# M720.net
KiCad netlist of a schematic drawn in EAGLE
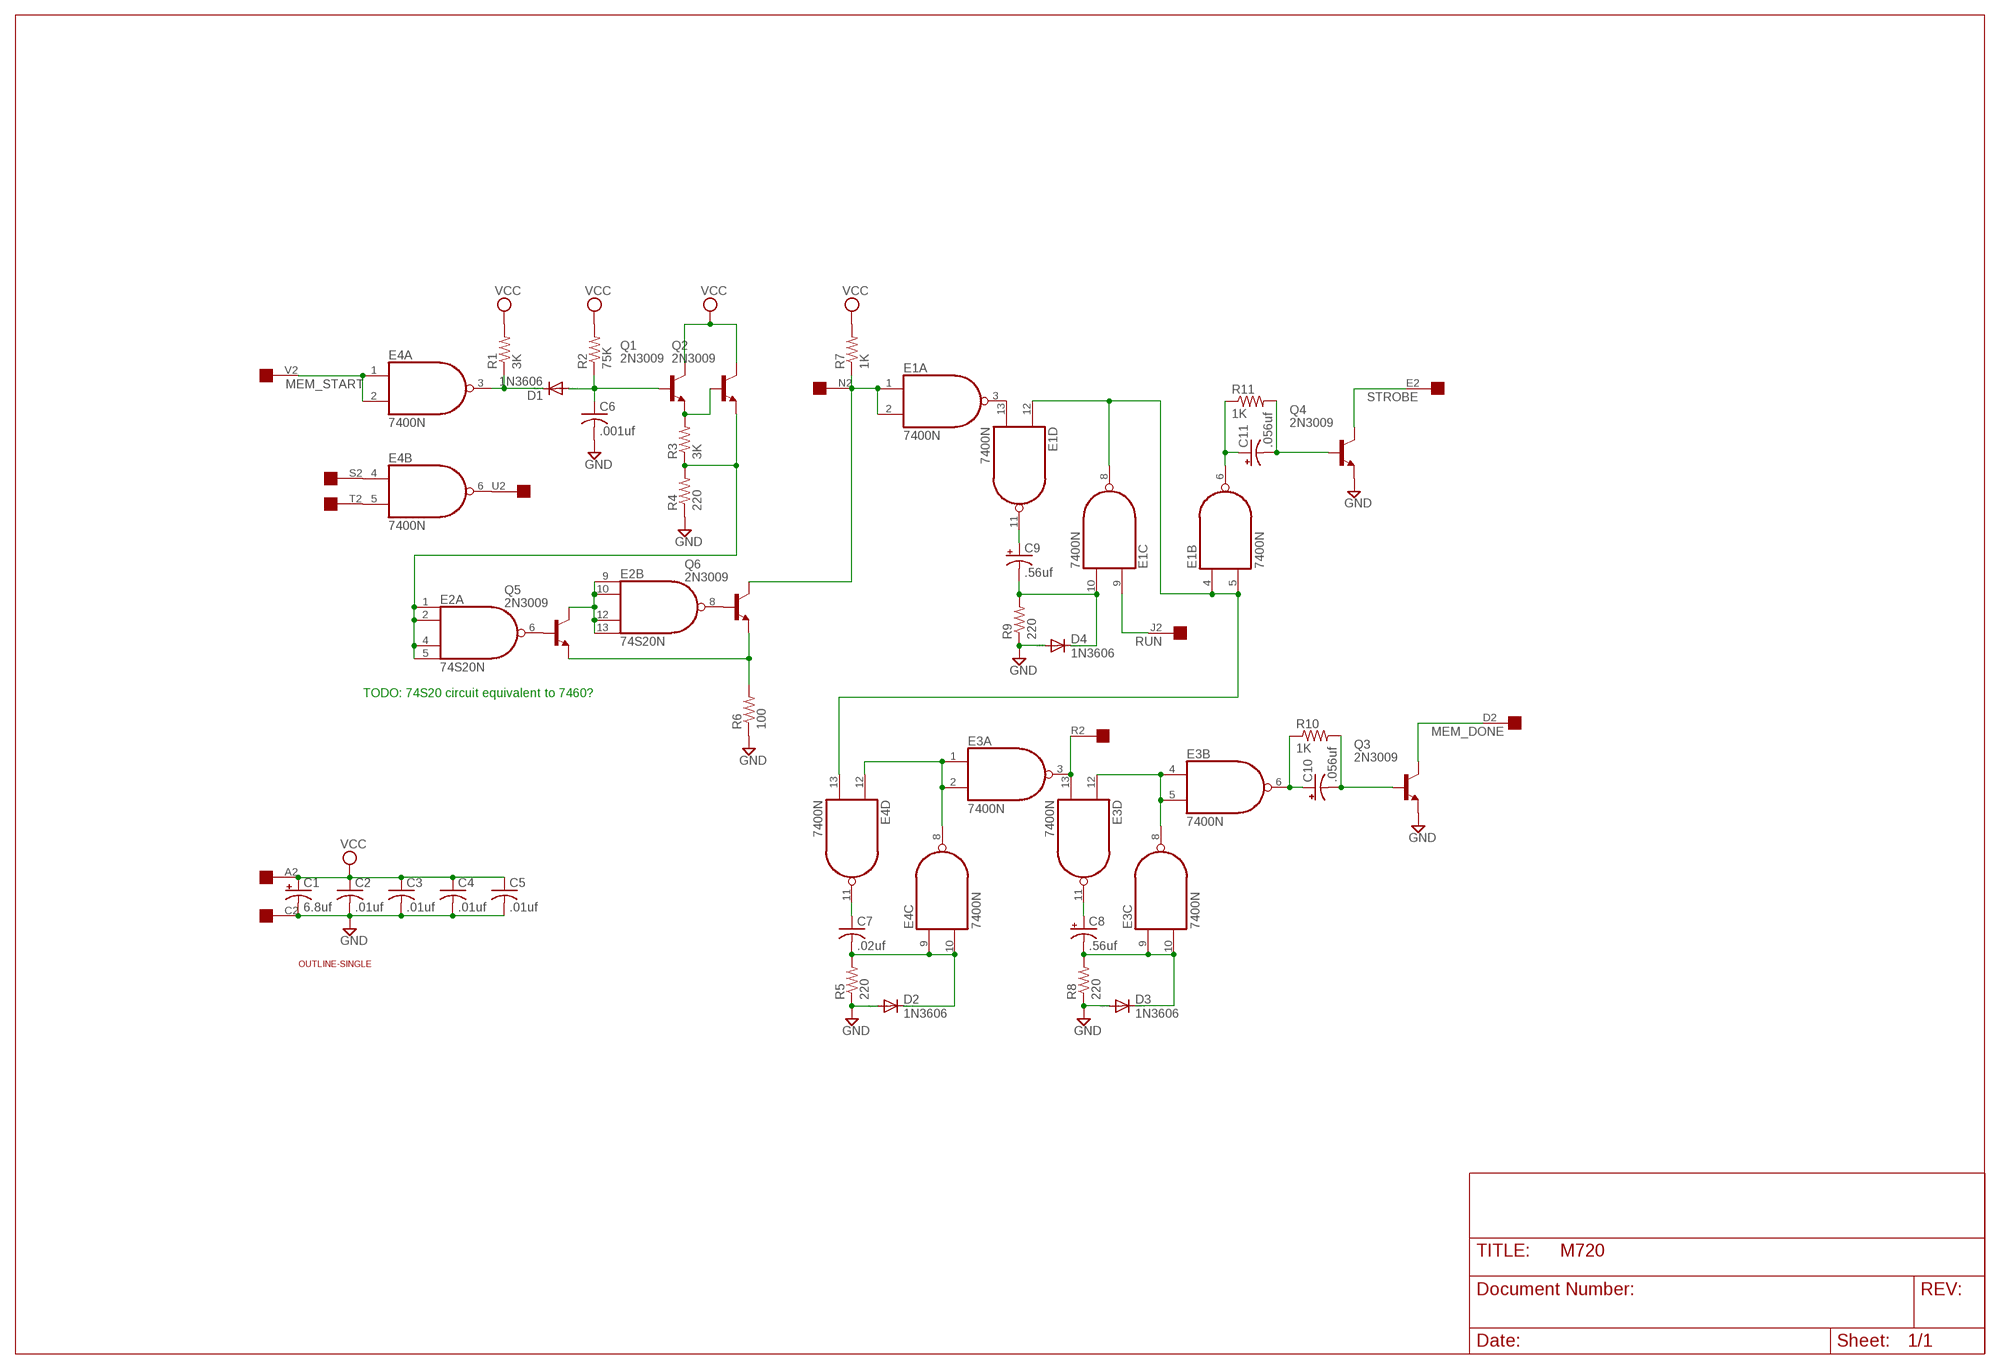
[diagram p0: schematic, sheet 1]

(export (version "E")
  (design (tool "Eeschema 10.0.6"))
  (components
    (comp (ref "C1")
      (value "6.8uf")
      (footprint "eagle-import:E15-5")
      (libsource (lib "eagle-import") (part "CPOL-USE15-5AXIAL"))
    )
    (comp (ref "C2")
      (value ".01uf")
      (footprint "eagle-import:C050-025X075")
      (libsource (lib "eagle-import") (part "C-US050-025X075"))
    )
    (comp (ref "C3")
      (value ".01uf")
      (footprint "eagle-import:C050-025X075")
      (libsource (lib "eagle-import") (part "C-US050-025X075"))
    )
    (comp (ref "C4")
      (value ".01uf")
      (footprint "eagle-import:C050-025X075")
      (libsource (lib "eagle-import") (part "C-US050-025X075"))
    )
    (comp (ref "C5")
      (value ".01uf")
      (footprint "eagle-import:C050-025X075")
      (libsource (lib "eagle-import") (part "C-US050-025X075"))
    )
    (comp (ref "C6")
      (value ".001uf")
      (footprint "eagle-import:C050-025X075")
      (libsource (lib "eagle-import") (part "C-US050-025X075"))
    )
    (comp (ref "C7")
      (value ".02uf")
      (footprint "eagle-import:C050-025X075")
      (libsource (lib "eagle-import") (part "C-US050-025X075"))
    )
    (comp (ref "C8")
      (value ".56uf")
      (footprint "eagle-import:B45181C")
      (libsource (lib "eagle-import") (part "CPOL-USB45181C"))
    )
    (comp (ref "C9")
      (value ".56uf")
      (footprint "eagle-import:B45181C")
      (libsource (lib "eagle-import") (part "CPOL-USB45181C"))
    )
    (comp (ref "C10")
      (value ".056uf")
      (footprint "eagle-import:B45181C")
      (libsource (lib "eagle-import") (part "CPOL-USB45181C"))
    )
    (comp (ref "C11")
      (value ".056uf")
      (footprint "eagle-import:B45181C")
      (libsource (lib "eagle-import") (part "CPOL-USB45181C"))
    )
    (comp (ref "D1")
      (value "1N3606")
      (footprint "eagle-import:DO35-10")
      (libsource (lib "eagle-import") (part "1N4148DO35-10"))
    )
    (comp (ref "D2")
      (value "1N3606")
      (footprint "eagle-import:DO35-10")
      (libsource (lib "eagle-import") (part "1N4148DO35-10"))
    )
    (comp (ref "D3")
      (value "1N3606")
      (footprint "eagle-import:DO35-10")
      (libsource (lib "eagle-import") (part "1N4148DO35-10"))
    )
    (comp (ref "D4")
      (value "1N3606")
      (footprint "eagle-import:DO35-10")
      (libsource (lib "eagle-import") (part "1N4148DO35-10"))
    )
    (comp (ref "E1")
      (value "7400N")
      (footprint "eagle-import:DIL14")
      (libsource (lib "eagle-import") (part "7400N"))
    )
    (comp (ref "E2")
      (value "74S20N")
      (footprint "eagle-import:DIL14")
      (libsource (lib "eagle-import") (part "7420NS"))
    )
    (comp (ref "E3")
      (value "7400N")
      (footprint "eagle-import:DIL14")
      (libsource (lib "eagle-import") (part "7400N"))
    )
    (comp (ref "E4")
      (value "7400N")
      (footprint "eagle-import:DIL14")
      (libsource (lib "eagle-import") (part "7400N"))
    )
    (comp (ref "Q1")
      (value "2N3009")
      (footprint "eagle-import:TO5")
      (libsource (lib "eagle-import") (part "2N2405"))
    )
    (comp (ref "Q2")
      (value "2N3009")
      (footprint "eagle-import:TO5")
      (libsource (lib "eagle-import") (part "2N2405"))
    )
    (comp (ref "Q3")
      (value "2N3009")
      (footprint "eagle-import:TO5")
      (libsource (lib "eagle-import") (part "2N2405"))
    )
    (comp (ref "Q4")
      (value "2N3009")
      (footprint "eagle-import:TO5")
      (libsource (lib "eagle-import") (part "2N2405"))
    )
    (comp (ref "Q5")
      (value "2N3009")
      (footprint "eagle-import:TO5")
      (libsource (lib "eagle-import") (part "2N2405"))
    )
    (comp (ref "Q6")
      (value "2N3009")
      (footprint "eagle-import:TO5")
      (libsource (lib "eagle-import") (part "2N2405"))
    )
    (comp (ref "R1")
      (value "3K")
      (footprint "eagle-import:0207_10")
      (libsource (lib "eagle-import") (part "R-US_0207/10"))
    )
    (comp (ref "R2")
      (value "75K")
      (footprint "eagle-import:0207_10")
      (libsource (lib "eagle-import") (part "R-US_0207/10"))
    )
    (comp (ref "R3")
      (value "3K")
      (footprint "eagle-import:0207_10")
      (libsource (lib "eagle-import") (part "R-US_0207/10"))
    )
    (comp (ref "R4")
      (value "220")
      (footprint "eagle-import:0207_10")
      (libsource (lib "eagle-import") (part "R-US_0207/10"))
    )
    (comp (ref "R5")
      (value "220")
      (footprint "eagle-import:0207_10")
      (libsource (lib "eagle-import") (part "R-US_0207/10"))
    )
    (comp (ref "R6")
      (value "100")
      (footprint "eagle-import:0207_10")
      (libsource (lib "eagle-import") (part "R-US_0207/10"))
    )
    (comp (ref "R7")
      (value "1K")
      (footprint "eagle-import:0207_10")
      (libsource (lib "eagle-import") (part "R-US_0207/10"))
    )
    (comp (ref "R8")
      (value "220")
      (footprint "eagle-import:0207_10")
      (libsource (lib "eagle-import") (part "R-US_0207/10"))
    )
    (comp (ref "R9")
      (value "220")
      (footprint "eagle-import:0207_10")
      (libsource (lib "eagle-import") (part "R-US_0207/10"))
    )
    (comp (ref "R10")
      (value "1K")
      (footprint "eagle-import:0207_10")
      (libsource (lib "eagle-import") (part "R-US_0207/10"))
    )
    (comp (ref "R11")
      (value "1K")
      (footprint "eagle-import:0207_10")
      (libsource (lib "eagle-import") (part "R-US_0207/10"))
    )
    (comp (ref "U$1")
      (value "OUTLINE-SINGLE")
      (footprint "eagle-import:SINGLE")
      (libsource (lib "eagle-import") (part "OUTLINE-SINGLE"))
    )
    (comp (ref "U$3")
      (value "EDGE-1")
      (footprint "eagle-import:EDGE-CON1")
      (libsource (lib "eagle-import") (part "EDGE-1"))
    )
  )
  (nets
    (net (code "1") (name "/MEM_DONE") (class "Default")
      (node (ref "Q3") (pin "3") (pinfunction "C_3") (pintype "passive"))
      (node (ref "U$3") (pin "D2") (pinfunction "1_D2") (pintype "bidirectional"))
    )
    (net (code "2") (name "/MEM_START") (class "Default")
      (node (ref "E4") (pin "1") (pinfunction "I0_1") (pintype "input"))
      (node (ref "E4") (pin "2") (pinfunction "I1_2") (pintype "input"))
      (node (ref "U$3") (pin "V2") (pinfunction "1_V2") (pintype "bidirectional"))
    )
    (net (code "3") (name "/RUN") (class "Default")
      (node (ref "E1") (pin "9") (pinfunction "I0_9") (pintype "input"))
      (node (ref "U$3") (pin "J2") (pinfunction "1_J2") (pintype "bidirectional"))
    )
    (net (code "4") (name "/STROBE") (class "Default")
      (node (ref "Q4") (pin "3") (pinfunction "C_3") (pintype "passive"))
      (node (ref "U$3") (pin "E2") (pinfunction "1_E2") (pintype "bidirectional"))
    )
    (net (code "5") (name "GND") (class "Default")
      (node (ref "C1") (pin "-") (pinfunction "-_-") (pintype "passive"))
      (node (ref "C2") (pin "2") (pinfunction "2_2") (pintype "passive"))
      (node (ref "C3") (pin "2") (pinfunction "2_2") (pintype "passive"))
      (node (ref "C4") (pin "2") (pinfunction "2_2") (pintype "passive"))
      (node (ref "C5") (pin "2") (pinfunction "2_2") (pintype "passive"))
      (node (ref "C6") (pin "2") (pinfunction "2_2") (pintype "passive"))
      (node (ref "D2") (pin "A") (pinfunction "A_A") (pintype "passive"))
      (node (ref "D3") (pin "A") (pinfunction "A_A") (pintype "passive"))
      (node (ref "D4") (pin "A") (pinfunction "A_A") (pintype "passive"))
      (node (ref "Q3") (pin "1") (pinfunction "E_1") (pintype "passive"))
      (node (ref "Q4") (pin "1") (pinfunction "E_1") (pintype "passive"))
      (node (ref "R4") (pin "1") (pinfunction "1_1") (pintype "passive"))
      (node (ref "R5") (pin "1") (pinfunction "1_1") (pintype "passive"))
      (node (ref "R6") (pin "1") (pinfunction "1_1") (pintype "passive"))
      (node (ref "R8") (pin "1") (pinfunction "1_1") (pintype "passive"))
      (node (ref "R9") (pin "1") (pinfunction "1_1") (pintype "passive"))
      (node (ref "U$3") (pin "C2") (pinfunction "1_C2") (pintype "bidirectional"))
    )
    (net (code "6") (name "Net-(E1A-I0)") (class "Default")
      (node (ref "E1") (pin "1") (pinfunction "I0_1") (pintype "input"))
      (node (ref "E1") (pin "2") (pinfunction "I1_2") (pintype "input"))
      (node (ref "Q6") (pin "3") (pinfunction "C_3") (pintype "passive"))
      (node (ref "R7") (pin "1") (pinfunction "1_1") (pintype "passive"))
      (node (ref "U$3") (pin "N2") (pinfunction "1_N2") (pintype "bidirectional"))
    )
    (net (code "7") (name "Net-(E1A-O)") (class "Default")
      (node (ref "E1") (pin "13") (pinfunction "I1_13") (pintype "input"))
      (node (ref "E1") (pin "3") (pinfunction "O_3") (pintype "output"))
    )
    (net (code "8") (name "Net-(E1B-I0)") (class "Default")
      (node (ref "E1") (pin "12") (pinfunction "I0_12") (pintype "input"))
      (node (ref "E1") (pin "4") (pinfunction "I0_4") (pintype "input"))
      (node (ref "E1") (pin "5") (pinfunction "I1_5") (pintype "input"))
      (node (ref "E1") (pin "8") (pinfunction "O_8") (pintype "output"))
      (node (ref "E4") (pin "13") (pinfunction "I1_13") (pintype "input"))
    )
    (net (code "9") (name "Net-(E1B-O)") (class "Default")
      (node (ref "C11") (pin "+") (pinfunction "+_+") (pintype "passive"))
      (node (ref "E1") (pin "6") (pinfunction "O_6") (pintype "output"))
      (node (ref "R11") (pin "1") (pinfunction "1_1") (pintype "passive"))
    )
    (net (code "10") (name "Net-(E1C-I1)") (class "Default")
      (node (ref "C9") (pin "-") (pinfunction "-_-") (pintype "passive"))
      (node (ref "D4") (pin "C") (pinfunction "C_C") (pintype "passive"))
      (node (ref "E1") (pin "10") (pinfunction "I1_10") (pintype "input"))
      (node (ref "R9") (pin "2") (pinfunction "2_2") (pintype "passive"))
    )
    (net (code "11") (name "Net-(E1D-O)") (class "Default")
      (node (ref "C9") (pin "+") (pinfunction "+_+") (pintype "passive"))
      (node (ref "E1") (pin "11") (pinfunction "O_11") (pintype "output"))
    )
    (net (code "12") (name "Net-(E2A-I0)") (class "Default")
      (node (ref "E2") (pin "1") (pinfunction "I0_1") (pintype "input"))
      (node (ref "E2") (pin "2") (pinfunction "I1_2") (pintype "input"))
      (node (ref "E2") (pin "4") (pinfunction "I2_4") (pintype "input"))
      (node (ref "E2") (pin "5") (pinfunction "I3_5") (pintype "input"))
      (node (ref "Q2") (pin "1") (pinfunction "E_1") (pintype "passive"))
      (node (ref "R3") (pin "1") (pinfunction "1_1") (pintype "passive"))
      (node (ref "R4") (pin "2") (pinfunction "2_2") (pintype "passive"))
    )
    (net (code "13") (name "Net-(E2A-O)") (class "Default")
      (node (ref "E2") (pin "6") (pinfunction "O_6") (pintype "output"))
      (node (ref "Q5") (pin "2") (pinfunction "B_2") (pintype "passive"))
    )
    (net (code "14") (name "Net-(E2B-I0)") (class "Default")
      (node (ref "E2") (pin "10") (pinfunction "I1_10") (pintype "input"))
      (node (ref "E2") (pin "12") (pinfunction "I2_12") (pintype "input"))
      (node (ref "E2") (pin "13") (pinfunction "I3_13") (pintype "input"))
      (node (ref "E2") (pin "9") (pinfunction "I0_9") (pintype "input"))
      (node (ref "Q5") (pin "3") (pinfunction "C_3") (pintype "passive"))
    )
    (net (code "15") (name "Net-(E2B-O)") (class "Default")
      (node (ref "E2") (pin "8") (pinfunction "O_8") (pintype "output"))
      (node (ref "Q6") (pin "2") (pinfunction "B_2") (pintype "passive"))
    )
    (net (code "16") (name "Net-(E3A-I0)") (class "Default")
      (node (ref "E3") (pin "1") (pinfunction "I0_1") (pintype "input"))
      (node (ref "E3") (pin "2") (pinfunction "I1_2") (pintype "input"))
      (node (ref "E4") (pin "12") (pinfunction "I0_12") (pintype "input"))
      (node (ref "E4") (pin "8") (pinfunction "O_8") (pintype "output"))
    )
    (net (code "17") (name "Net-(E3A-O)") (class "Default")
      (node (ref "E3") (pin "13") (pinfunction "I1_13") (pintype "input"))
      (node (ref "E3") (pin "3") (pinfunction "O_3") (pintype "output"))
      (node (ref "U$3") (pin "R2") (pinfunction "1_R2") (pintype "bidirectional"))
    )
    (net (code "18") (name "Net-(E3B-I0)") (class "Default")
      (node (ref "E3") (pin "12") (pinfunction "I0_12") (pintype "input"))
      (node (ref "E3") (pin "4") (pinfunction "I0_4") (pintype "input"))
      (node (ref "E3") (pin "5") (pinfunction "I1_5") (pintype "input"))
      (node (ref "E3") (pin "8") (pinfunction "O_8") (pintype "output"))
    )
    (net (code "19") (name "Net-(E3B-O)") (class "Default")
      (node (ref "C10") (pin "+") (pinfunction "+_+") (pintype "passive"))
      (node (ref "E3") (pin "6") (pinfunction "O_6") (pintype "output"))
      (node (ref "R10") (pin "1") (pinfunction "1_1") (pintype "passive"))
    )
    (net (code "20") (name "Net-(E3C-I0)") (class "Default")
      (node (ref "C8") (pin "-") (pinfunction "-_-") (pintype "passive"))
      (node (ref "D3") (pin "C") (pinfunction "C_C") (pintype "passive"))
      (node (ref "E3") (pin "10") (pinfunction "I1_10") (pintype "input"))
      (node (ref "E3") (pin "9") (pinfunction "I0_9") (pintype "input"))
      (node (ref "R8") (pin "2") (pinfunction "2_2") (pintype "passive"))
    )
    (net (code "21") (name "Net-(E3D-O)") (class "Default")
      (node (ref "C8") (pin "+") (pinfunction "+_+") (pintype "passive"))
      (node (ref "E3") (pin "11") (pinfunction "O_11") (pintype "output"))
    )
    (net (code "22") (name "Net-(E4A-O)") (class "Default")
      (node (ref "D1") (pin "C") (pinfunction "C_C") (pintype "passive"))
      (node (ref "E4") (pin "3") (pinfunction "O_3") (pintype "output"))
      (node (ref "R1") (pin "1") (pinfunction "1_1") (pintype "passive"))
    )
    (net (code "23") (name "Net-(E4B-I0)") (class "Default")
      (node (ref "E4") (pin "4") (pinfunction "I0_4") (pintype "input"))
      (node (ref "U$3") (pin "S2") (pinfunction "1_S2") (pintype "bidirectional"))
    )
    (net (code "24") (name "Net-(E4B-I1)") (class "Default")
      (node (ref "E4") (pin "5") (pinfunction "I1_5") (pintype "input"))
      (node (ref "U$3") (pin "T2") (pinfunction "1_T2") (pintype "bidirectional"))
    )
    (net (code "25") (name "Net-(E4B-O)") (class "Default")
      (node (ref "E4") (pin "6") (pinfunction "O_6") (pintype "output"))
      (node (ref "U$3") (pin "U2") (pinfunction "1_U2") (pintype "bidirectional"))
    )
    (net (code "26") (name "Net-(E4C-I0)") (class "Default")
      (node (ref "C7") (pin "2") (pinfunction "2_2") (pintype "passive"))
      (node (ref "D2") (pin "C") (pinfunction "C_C") (pintype "passive"))
      (node (ref "E4") (pin "10") (pinfunction "I1_10") (pintype "input"))
      (node (ref "E4") (pin "9") (pinfunction "I0_9") (pintype "input"))
      (node (ref "R5") (pin "2") (pinfunction "2_2") (pintype "passive"))
    )
    (net (code "27") (name "Net-(E4D-O)") (class "Default")
      (node (ref "C7") (pin "1") (pinfunction "1_1") (pintype "passive"))
      (node (ref "E4") (pin "11") (pinfunction "O_11") (pintype "output"))
    )
    (net (code "28") (name "Net-(Q1-B)") (class "Default")
      (node (ref "C6") (pin "1") (pinfunction "1_1") (pintype "passive"))
      (node (ref "D1") (pin "A") (pinfunction "A_A") (pintype "passive"))
      (node (ref "Q1") (pin "2") (pinfunction "B_2") (pintype "passive"))
      (node (ref "R2") (pin "1") (pinfunction "1_1") (pintype "passive"))
    )
    (net (code "29") (name "Net-(Q1-E)") (class "Default")
      (node (ref "Q1") (pin "1") (pinfunction "E_1") (pintype "passive"))
      (node (ref "Q2") (pin "2") (pinfunction "B_2") (pintype "passive"))
      (node (ref "R3") (pin "2") (pinfunction "2_2") (pintype "passive"))
    )
    (net (code "30") (name "Net-(Q3-B)") (class "Default")
      (node (ref "C10") (pin "-") (pinfunction "-_-") (pintype "passive"))
      (node (ref "Q3") (pin "2") (pinfunction "B_2") (pintype "passive"))
      (node (ref "R10") (pin "2") (pinfunction "2_2") (pintype "passive"))
    )
    (net (code "31") (name "Net-(Q4-B)") (class "Default")
      (node (ref "C11") (pin "-") (pinfunction "-_-") (pintype "passive"))
      (node (ref "Q4") (pin "2") (pinfunction "B_2") (pintype "passive"))
      (node (ref "R11") (pin "2") (pinfunction "2_2") (pintype "passive"))
    )
    (net (code "32") (name "Net-(Q5-E)") (class "Default")
      (node (ref "Q5") (pin "1") (pinfunction "E_1") (pintype "passive"))
      (node (ref "Q6") (pin "1") (pinfunction "E_1") (pintype "passive"))
      (node (ref "R6") (pin "2") (pinfunction "2_2") (pintype "passive"))
    )
    (net (code "33") (name "VCC") (class "Default")
      (node (ref "C1") (pin "+") (pinfunction "+_+") (pintype "passive"))
      (node (ref "C2") (pin "1") (pinfunction "1_1") (pintype "passive"))
      (node (ref "C3") (pin "1") (pinfunction "1_1") (pintype "passive"))
      (node (ref "C4") (pin "1") (pinfunction "1_1") (pintype "passive"))
      (node (ref "C5") (pin "1") (pinfunction "1_1") (pintype "passive"))
      (node (ref "Q1") (pin "3") (pinfunction "C_3") (pintype "passive"))
      (node (ref "Q2") (pin "3") (pinfunction "C_3") (pintype "passive"))
      (node (ref "R1") (pin "2") (pinfunction "2_2") (pintype "passive"))
      (node (ref "R2") (pin "2") (pinfunction "2_2") (pintype "passive"))
      (node (ref "R7") (pin "2") (pinfunction "2_2") (pintype "passive"))
      (node (ref "U$3") (pin "A2") (pinfunction "1_A2") (pintype "bidirectional"))
    )
  )
)
